# design.net
KiCad netlist of a schematic drawn in Altium Designer
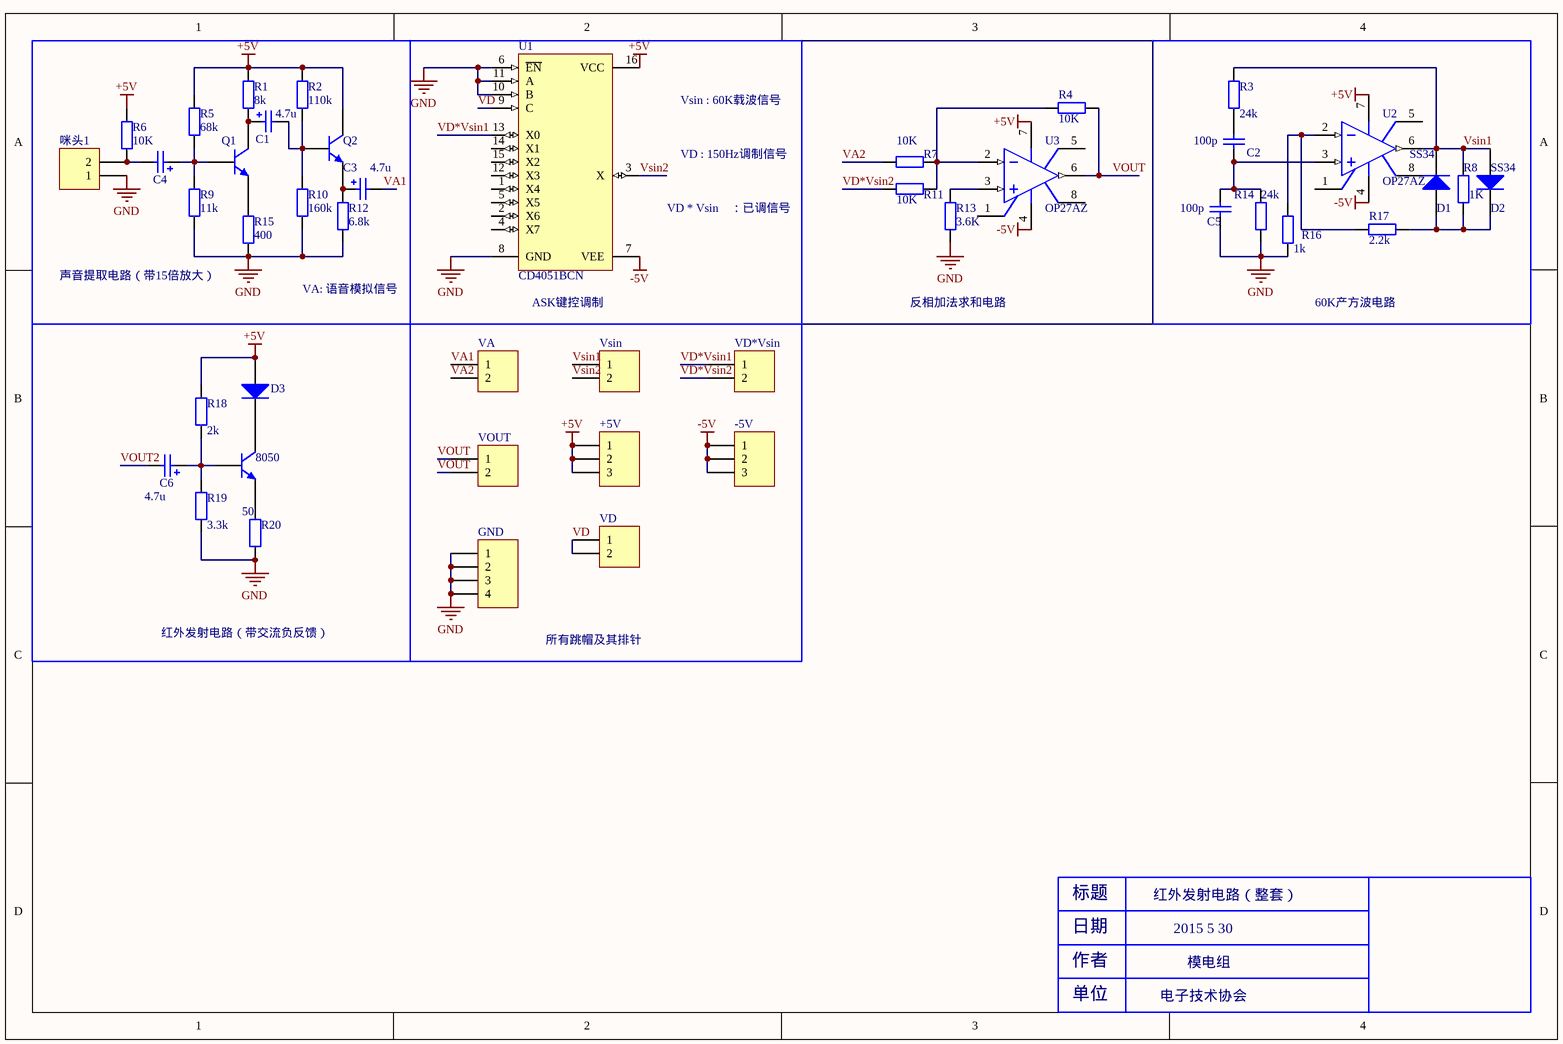
[diagram p0: 红外发射（整套）.SchDoc]

(export (version "E")
  (design (tool "Eeschema 10.0.6"))
  (components
    (comp (ref "+5V")
      (value "Header 3")
      (footprint "HDR1X3")
      (description "Header, 3-Pin")
      (fields (field (name "PUBLISHER") "Altium Limited"))
      (libsource (lib "Miscellaneous Connectors") (part "Header 3"))
    )
    (comp (ref "-5V")
      (value "Header 3")
      (footprint "HDR1X3")
      (description "Header, 3-Pin")
      (fields (field (name "PUBLISHER") "Altium Limited"))
      (libsource (lib "Miscellaneous Connectors") (part "Header 3"))
    )
    (comp (ref "8050")
      (value "NPN")
      (footprint "TO-226")
      (description "NPN Bipolar Transistor")
      (fields (field (name "PUBLISHER") "Altium Limited"))
      (libsource (lib "Miscellaneous Devices") (part "NPN"))
    )
    (comp (ref "C1")
      (value "电解电容")
      (footprint "电解电容")
      (fields (field (name "ALTIUM_UNNAMED_1") "4.7u"))
      (libsource (lib "自制库（原理图文件）") (part "电解电容"))
    )
    (comp (ref "C2")
      (value "瓷片电容")
      (footprint "瓷片电容")
      (fields (field (name "ALTIUM_UNNAMED_1") "100p"))
      (libsource (lib "自制库（原理图文件）") (part "瓷片电容"))
    )
    (comp (ref "C3")
      (value "电解电容")
      (footprint "电解电容")
      (fields (field (name "ALTIUM_UNNAMED_1") "4.7u"))
      (libsource (lib "自制库（原理图文件）") (part "电解电容"))
    )
    (comp (ref "C4") (value "电解电容") (footprint "电解电容") (libsource (lib "自制库（原理图文件）") (part "电解电容")))
    (comp (ref "C5")
      (value "瓷片电容")
      (footprint "瓷片电容")
      (fields (field (name "ALTIUM_UNNAMED_1") "100p"))
      (libsource (lib "自制库（原理图文件）") (part "瓷片电容"))
    )
    (comp (ref "C6")
      (value "电解电容")
      (footprint "电解电容")
      (fields (field (name "ALTIUM_UNNAMED_1") "4.7u"))
      (libsource (lib "自制库（原理图文件）") (part "电解电容"))
    )
    (comp (ref "D1")
      (value "SS34")
      (footprint "DO-41")
      (description "1 Amp General Purpose Rectifier")
      (fields (field (name "PUBLISHER") "Altium Limited"))
      (libsource (lib "Miscellaneous Devices") (part "Diode 1N4007"))
    )
    (comp (ref "D2")
      (value "SS34")
      (footprint "DO-41")
      (description "1 Amp General Purpose Rectifier")
      (fields (field (name "PUBLISHER") "Altium Limited"))
      (libsource (lib "Miscellaneous Devices") (part "Diode 1N4007"))
    )
    (comp (ref "D3")
      (value "Diode")
      (footprint "SMC")
      (description "Default Diode")
      (fields (field (name "PUBLISHER") "Altium Limited"))
      (libsource (lib "Miscellaneous Devices") (part "Diode"))
    )
    (comp (ref "GND")
      (value "Header 4")
      (footprint "HDR1X4")
      (description "Header, 4-Pin")
      (fields (field (name "PUBLISHER") "Altium Limited"))
      (libsource (lib "Miscellaneous Connectors") (part "Header 4"))
    )
    (comp (ref "Q1")
      (value "NPN")
      (footprint "TO-92A")
      (description "NPN Bipolar Transistor")
      (fields (field (name "PUBLISHER") "Altium Limited"))
      (libsource (lib "Miscellaneous Devices") (part "NPN"))
    )
    (comp (ref "Q2")
      (value "NPN")
      (footprint "TO-92A")
      (description "NPN Bipolar Transistor")
      (fields (field (name "PUBLISHER") "Altium Limited"))
      (libsource (lib "Miscellaneous Devices") (part "NPN"))
    )
    (comp (ref "R1")
      (value "8k")
      (footprint "AXIAL-0.4")
      (description "Resistor")
      (fields (field (name "Comment") "Res2") (field (name "PUBLISHER") "Altium Limited"))
      (libsource (lib "") (part "Res2_1"))
    )
    (comp (ref "R2")
      (value "110k")
      (footprint "AXIAL-0.4")
      (description "Resistor")
      (fields (field (name "Comment") "Res2") (field (name "PUBLISHER") "Altium Limited"))
      (libsource (lib "") (part "Res2_1"))
    )
    (comp (ref "R3")
      (value "24k")
      (footprint "AXIAL-0.4")
      (description "Resistor")
      (fields (field (name "Comment") "Res2") (field (name "PUBLISHER") "Altium Limited"))
      (libsource (lib "") (part "Res2_1"))
    )
    (comp (ref "R4")
      (value "10K")
      (footprint "AXIAL-0.4")
      (description "Resistor")
      (fields (field (name "Comment") "Res2") (field (name "PUBLISHER") "Altium Limited"))
      (libsource (lib "Miscellaneous Devices") (part "Res2"))
    )
    (comp (ref "R5")
      (value "68k")
      (footprint "AXIAL-0.4")
      (description "Resistor")
      (fields (field (name "Comment") "Res2") (field (name "PUBLISHER") "Altium Limited"))
      (libsource (lib "") (part "Res2_1"))
    )
    (comp (ref "R6")
      (value "10K")
      (footprint "AXIAL-0.4")
      (description "Resistor")
      (fields (field (name "Comment") "Res2") (field (name "PUBLISHER") "Altium Limited"))
      (libsource (lib "") (part "Res2_1"))
    )
    (comp (ref "R7")
      (value "10K")
      (footprint "AXIAL-0.4")
      (description "Resistor")
      (fields (field (name "Comment") "Res2") (field (name "PUBLISHER") "Altium Limited"))
      (libsource (lib "Miscellaneous Devices") (part "Res2"))
    )
    (comp (ref "R8")
      (value "1K")
      (footprint "AXIAL-0.4")
      (description "Resistor")
      (fields (field (name "Comment") "Res2") (field (name "PUBLISHER") "Altium Limited"))
      (libsource (lib "") (part "Res2_1"))
    )
    (comp (ref "R9")
      (value "11k")
      (footprint "AXIAL-0.4")
      (description "Resistor")
      (fields (field (name "Comment") "Res2") (field (name "PUBLISHER") "Altium Limited"))
      (libsource (lib "") (part "Res2_1"))
    )
    (comp (ref "R10")
      (value "160k")
      (footprint "AXIAL-0.4")
      (description "Resistor")
      (fields (field (name "Comment") "Res2") (field (name "PUBLISHER") "Altium Limited"))
      (libsource (lib "") (part "Res2_1"))
    )
    (comp (ref "R11")
      (value "10K")
      (footprint "AXIAL-0.4")
      (description "Resistor")
      (fields (field (name "Comment") "Res2") (field (name "PUBLISHER") "Altium Limited"))
      (libsource (lib "Miscellaneous Devices") (part "Res2"))
    )
    (comp (ref "R12")
      (value "6.8k")
      (footprint "AXIAL-0.4")
      (description "Resistor")
      (fields (field (name "Comment") "Res2") (field (name "PUBLISHER") "Altium Limited"))
      (libsource (lib "") (part "Res2_1"))
    )
    (comp (ref "R13")
      (value "3.6K")
      (footprint "AXIAL-0.4")
      (description "Resistor")
      (fields (field (name "Comment") "Res2") (field (name "PUBLISHER") "Altium Limited"))
      (libsource (lib "") (part "Res2_1"))
    )
    (comp (ref "R14")
      (value "24k")
      (footprint "AXIAL-0.4")
      (description "Resistor")
      (fields (field (name "Comment") "Res2") (field (name "PUBLISHER") "Altium Limited"))
      (libsource (lib "") (part "Res2_1"))
    )
    (comp (ref "R15")
      (value "400")
      (footprint "AXIAL-0.4")
      (description "Resistor")
      (fields (field (name "Comment") "Res2") (field (name "PUBLISHER") "Altium Limited"))
      (libsource (lib "") (part "Res2_1"))
    )
    (comp (ref "R16")
      (value "1k")
      (footprint "AXIAL-0.4")
      (description "Resistor")
      (fields (field (name "Comment") "Res2") (field (name "PUBLISHER") "Altium Limited"))
      (libsource (lib "") (part "Res2_1"))
    )
    (comp (ref "R17")
      (value "2.2k")
      (footprint "AXIAL-0.4")
      (description "Resistor")
      (fields (field (name "Comment") "Res2") (field (name "PUBLISHER") "Altium Limited"))
      (libsource (lib "Miscellaneous Devices") (part "Res2"))
    )
    (comp (ref "R18")
      (value "2k")
      (footprint "AXIAL-0.4")
      (description "Resistor")
      (fields (field (name "Comment") "Res2") (field (name "PUBLISHER") "Altium Limited"))
      (libsource (lib "") (part "Res2_1"))
    )
    (comp (ref "R19")
      (value "3.3k")
      (footprint "AXIAL-0.4")
      (description "Resistor")
      (fields (field (name "Comment") "Res2") (field (name "PUBLISHER") "Altium Limited"))
      (libsource (lib "") (part "Res2_1"))
    )
    (comp (ref "R20")
      (value "50")
      (footprint "AXIAL-0.4")
      (description "Resistor")
      (fields (field (name "Comment") "Res2") (field (name "PUBLISHER") "Altium Limited"))
      (libsource (lib "") (part "Res2_1"))
    )
    (comp (ref "U1")
      (value "CD4051BCN")
      (footprint "DIP16")
      (description "8-Channel Analog Multiplexer/Demultiplexer")
      (fields (field (name "PUBLISHER") "Altium Limited"))
      (libsource (lib "FSC Logic Multiplexer") (part "CD4051BCN"))
    )
    (comp (ref "U2")
      (value "OP27AZ")
      (footprint "DIP8")
      (description "Low-Noise, Precision Operational Amplifier")
      (fields (field (name "PUBLISHER") "Altium Limited"))
      (libsource (lib "AD Operational Amplifier") (part "OP27AZ"))
    )
    (comp (ref "U3")
      (value "OP27AZ")
      (footprint "DIP8")
      (description "Low-Noise, Precision Operational Amplifier")
      (fields (field (name "PUBLISHER") "Altium Limited"))
      (libsource (lib "AD Operational Amplifier") (part "OP27AZ"))
    )
    (comp (ref "VA")
      (value "Header 2")
      (footprint "HDR1X2")
      (description "Header, 2-Pin")
      (fields (field (name "PUBLISHER") "Altium Limited"))
      (libsource (lib "Miscellaneous Connectors") (part "Header 2"))
    )
    (comp (ref "VD")
      (value "Header 2")
      (footprint "HDR1X2")
      (description "Header, 2-Pin")
      (fields (field (name "PUBLISHER") "Altium Limited"))
      (libsource (lib "Miscellaneous Connectors") (part "Header 2"))
    )
    (comp (ref "VD*Vsin")
      (value "Header 2")
      (footprint "HDR1X2")
      (description "Header, 2-Pin")
      (fields (field (name "PUBLISHER") "Altium Limited"))
      (libsource (lib "Miscellaneous Connectors") (part "Header 2"))
    )
    (comp (ref "VOUT")
      (value "Header 2")
      (footprint "HDR1X2")
      (description "Header, 2-Pin")
      (fields (field (name "PUBLISHER") "Altium Limited"))
      (libsource (lib "Miscellaneous Connectors") (part "Header 2"))
    )
    (comp (ref "Vsin")
      (value "Header 2")
      (footprint "HDR1X2")
      (description "Header, 2-Pin")
      (fields (field (name "PUBLISHER") "Altium Limited"))
      (libsource (lib "Miscellaneous Connectors") (part "Header 2"))
    )
    (comp (ref "咪头1")
      (value "Header 2")
      (footprint "HDR1X2")
      (description "Header, 2-Pin")
      (fields (field (name "PUBLISHER") "Altium Limited"))
      (libsource (lib "") (part "Header 2_1"))
    )
  )
  (nets
    (net (code "1") (name "+5V") (class "Default")
      (node (ref "+5V") (pin "1") (pinfunction "1_1") (pintype "passive"))
      (node (ref "+5V") (pin "2") (pinfunction "2_2") (pintype "passive"))
      (node (ref "+5V") (pin "3") (pinfunction "3_3") (pintype "passive"))
      (node (ref "D3") (pin "1") (pinfunction "A_1") (pintype "passive"))
      (node (ref "Q2") (pin "1") (pinfunction "C_1") (pintype "passive"))
      (node (ref "R1") (pin "2") (pinfunction "2_2") (pintype "passive"))
      (node (ref "R18") (pin "2") (pinfunction "2_2") (pintype "passive"))
      (node (ref "R2") (pin "2") (pinfunction "2_2") (pintype "passive"))
      (node (ref "R5") (pin "2") (pinfunction "2_2") (pintype "passive"))
      (node (ref "R6") (pin "2") (pinfunction "2_2") (pintype "passive"))
      (node (ref "U1") (pin "16") (pinfunction "VCC_16") (pintype "power_in"))
      (node (ref "U2") (pin "7") (pinfunction "V+_7") (pintype "power_in"))
      (node (ref "U3") (pin "7") (pinfunction "V+_7") (pintype "power_in"))
    )
    (net (code "2") (name "-5V") (class "Default")
      (node (ref "-5V") (pin "1") (pinfunction "1_1") (pintype "passive"))
      (node (ref "-5V") (pin "2") (pinfunction "2_2") (pintype "passive"))
      (node (ref "-5V") (pin "3") (pinfunction "3_3") (pintype "passive"))
      (node (ref "U1") (pin "7") (pinfunction "VEE_7") (pintype "power_in"))
      (node (ref "U2") (pin "4") (pinfunction "V-_4") (pintype "power_in"))
      (node (ref "U3") (pin "4") (pinfunction "V-_4") (pintype "power_in"))
    )
    (net (code "3") (name "/VA1") (class "Default")
      (node (ref "C3") (pin "2") (pinfunction "2_2") (pintype "passive"))
      (node (ref "VA") (pin "1") (pinfunction "1_1") (pintype "passive"))
    )
    (net (code "4") (name "/VA2") (class "Default")
      (node (ref "R7") (pin "1") (pinfunction "1_1") (pintype "passive"))
      (node (ref "VA") (pin "2") (pinfunction "2_2") (pintype "passive"))
    )
    (net (code "5") (name "/VD") (class "Default")
      (node (ref "U1") (pin "9") (pinfunction "C_9") (pintype "input"))
      (node (ref "VD") (pin "1") (pinfunction "1_1") (pintype "passive"))
      (node (ref "VD") (pin "2") (pinfunction "2_2") (pintype "passive"))
    )
    (net (code "6") (name "/VD*Vsin1") (class "Default")
      (node (ref "U1") (pin "13") (pinfunction "X0_13") (pintype "bidirectional"))
      (node (ref "VD*Vsin") (pin "1") (pinfunction "1_1") (pintype "passive"))
    )
    (net (code "7") (name "/VD*Vsin2") (class "Default")
      (node (ref "R11") (pin "1") (pinfunction "1_1") (pintype "passive"))
      (node (ref "VD*Vsin") (pin "2") (pinfunction "2_2") (pintype "passive"))
    )
    (net (code "8") (name "/VOUT") (class "Default")
      (node (ref "R4") (pin "2") (pinfunction "2_2") (pintype "passive"))
      (node (ref "U3") (pin "6") (pinfunction "OUT_6") (pintype "output"))
      (node (ref "VOUT") (pin "1") (pinfunction "1_1") (pintype "passive"))
      (node (ref "VOUT") (pin "2") (pinfunction "2_2") (pintype "passive"))
    )
    (net (code "9") (name "/VOUT2") (class "Default")
      (node (ref "C6") (pin "2") (pinfunction "2_2") (pintype "passive"))
    )
    (net (code "10") (name "/Vsin1") (class "Default")
      (node (ref "D1") (pin "2") (pinfunction "K_2") (pintype "passive"))
      (node (ref "D2") (pin "1") (pinfunction "A_1") (pintype "passive"))
      (node (ref "R3") (pin "2") (pinfunction "2_2") (pintype "passive"))
      (node (ref "R8") (pin "2") (pinfunction "2_2") (pintype "passive"))
      (node (ref "U2") (pin "6") (pinfunction "OUT_6") (pintype "output"))
      (node (ref "Vsin") (pin "1") (pinfunction "1_1") (pintype "passive"))
    )
    (net (code "11") (name "/Vsin2") (class "Default")
      (node (ref "U1") (pin "3") (pinfunction "X_3") (pintype "bidirectional"))
      (node (ref "Vsin") (pin "2") (pinfunction "2_2") (pintype "passive"))
    )
    (net (code "12") (name "GND") (class "Default")
      (node (ref "C5") (pin "1") (pinfunction "1_1") (pintype "passive"))
      (node (ref "GND") (pin "1") (pinfunction "1_1") (pintype "passive"))
      (node (ref "GND") (pin "2") (pinfunction "2_2") (pintype "passive"))
      (node (ref "GND") (pin "3") (pinfunction "3_3") (pintype "passive"))
      (node (ref "GND") (pin "4") (pinfunction "4_4") (pintype "passive"))
      (node (ref "R10") (pin "1") (pinfunction "1_1") (pintype "passive"))
      (node (ref "R12") (pin "1") (pinfunction "1_1") (pintype "passive"))
      (node (ref "R13") (pin "1") (pinfunction "1_1") (pintype "passive"))
      (node (ref "R14") (pin "1") (pinfunction "1_1") (pintype "passive"))
      (node (ref "R15") (pin "1") (pinfunction "1_1") (pintype "passive"))
      (node (ref "R16") (pin "1") (pinfunction "1_1") (pintype "passive"))
      (node (ref "R19") (pin "1") (pinfunction "1_1") (pintype "passive"))
      (node (ref "R20") (pin "1") (pinfunction "1_1") (pintype "passive"))
      (node (ref "R9") (pin "1") (pinfunction "1_1") (pintype "passive"))
      (node (ref "U1") (pin "10") (pinfunction "B_10") (pintype "input"))
      (node (ref "U1") (pin "11") (pinfunction "A_11") (pintype "input"))
      (node (ref "U1") (pin "6") (pinfunction "~{EN}_6") (pintype "input"))
      (node (ref "U1") (pin "8") (pinfunction "GND_8") (pintype "power_in"))
      (node (ref "咪头1") (pin "1") (pinfunction "1_1") (pintype "passive"))
    )
    (net (code "13") (name "Net-(8050-B)") (class "Default")
      (node (ref "8050") (pin "2") (pinfunction "B_2") (pintype "passive"))
      (node (ref "C6") (pin "1") (pinfunction "1_1") (pintype "passive"))
      (node (ref "R18") (pin "1") (pinfunction "1_1") (pintype "passive"))
      (node (ref "R19") (pin "2") (pinfunction "2_2") (pintype "passive"))
    )
    (net (code "14") (name "Net-(8050-C)") (class "Default")
      (node (ref "8050") (pin "1") (pinfunction "C_1") (pintype "passive"))
      (node (ref "D3") (pin "2") (pinfunction "K_2") (pintype "passive"))
    )
    (net (code "15") (name "Net-(8050-E)") (class "Default")
      (node (ref "8050") (pin "3") (pinfunction "E_3") (pintype "passive"))
      (node (ref "R20") (pin "2") (pinfunction "2_2") (pintype "passive"))
    )
    (net (code "16") (name "Net-(C2-Pad2)") (class "Default")
      (node (ref "C2") (pin "2") (pinfunction "2_2") (pintype "passive"))
      (node (ref "R3") (pin "1") (pinfunction "1_1") (pintype "passive"))
    )
    (net (code "17") (name "Net-(C4-Pad2)") (class "Default")
      (node (ref "C4") (pin "2") (pinfunction "2_2") (pintype "passive"))
      (node (ref "R6") (pin "1") (pinfunction "1_1") (pintype "passive"))
      (node (ref "咪头1") (pin "2") (pinfunction "2_2") (pintype "passive"))
    )
    (net (code "18") (name "Net-(D1-A)") (class "Default")
      (node (ref "D1") (pin "1") (pinfunction "A_1") (pintype "passive"))
      (node (ref "D2") (pin "2") (pinfunction "K_2") (pintype "passive"))
      (node (ref "R17") (pin "2") (pinfunction "2_2") (pintype "passive"))
      (node (ref "R8") (pin "1") (pinfunction "1_1") (pintype "passive"))
    )
    (net (code "19") (name "Net-(Q1-B)") (class "Default")
      (node (ref "C4") (pin "1") (pinfunction "1_1") (pintype "passive"))
      (node (ref "Q1") (pin "2") (pinfunction "B_2") (pintype "passive"))
      (node (ref "R5") (pin "1") (pinfunction "1_1") (pintype "passive"))
      (node (ref "R9") (pin "2") (pinfunction "2_2") (pintype "passive"))
    )
    (net (code "20") (name "Net-(Q1-C)") (class "Default")
      (node (ref "C1") (pin "1") (pinfunction "1_1") (pintype "passive"))
      (node (ref "Q1") (pin "1") (pinfunction "C_1") (pintype "passive"))
      (node (ref "R1") (pin "1") (pinfunction "1_1") (pintype "passive"))
    )
    (net (code "21") (name "Net-(Q1-E)") (class "Default")
      (node (ref "Q1") (pin "3") (pinfunction "E_3") (pintype "passive"))
      (node (ref "R15") (pin "2") (pinfunction "2_2") (pintype "passive"))
    )
    (net (code "22") (name "Net-(Q2-B)") (class "Default")
      (node (ref "C1") (pin "2") (pinfunction "2_2") (pintype "passive"))
      (node (ref "Q2") (pin "2") (pinfunction "B_2") (pintype "passive"))
      (node (ref "R10") (pin "2") (pinfunction "2_2") (pintype "passive"))
      (node (ref "R2") (pin "1") (pinfunction "1_1") (pintype "passive"))
    )
    (net (code "23") (name "Net-(Q2-E)") (class "Default")
      (node (ref "C3") (pin "1") (pinfunction "1_1") (pintype "passive"))
      (node (ref "Q2") (pin "3") (pinfunction "E_3") (pintype "passive"))
      (node (ref "R12") (pin "2") (pinfunction "2_2") (pintype "passive"))
    )
    (net (code "24") (name "Net-(U2-IN+)") (class "Default")
      (node (ref "C2") (pin "1") (pinfunction "1_1") (pintype "passive"))
      (node (ref "C5") (pin "2") (pinfunction "2_2") (pintype "passive"))
      (node (ref "R14") (pin "2") (pinfunction "2_2") (pintype "passive"))
      (node (ref "U2") (pin "3") (pinfunction "IN+_3") (pintype "input"))
    )
    (net (code "25") (name "Net-(U2-IN-)") (class "Default")
      (node (ref "R16") (pin "2") (pinfunction "2_2") (pintype "passive"))
      (node (ref "R17") (pin "1") (pinfunction "1_1") (pintype "passive"))
      (node (ref "U2") (pin "2") (pinfunction "IN-_2") (pintype "input"))
    )
    (net (code "26") (name "Net-(U3-IN+)") (class "Default")
      (node (ref "R13") (pin "2") (pinfunction "2_2") (pintype "passive"))
      (node (ref "U3") (pin "3") (pinfunction "IN+_3") (pintype "input"))
    )
    (net (code "27") (name "Net-(U3-IN-)") (class "Default")
      (node (ref "R11") (pin "2") (pinfunction "2_2") (pintype "passive"))
      (node (ref "R4") (pin "1") (pinfunction "1_1") (pintype "passive"))
      (node (ref "R7") (pin "2") (pinfunction "2_2") (pintype "passive"))
      (node (ref "U3") (pin "2") (pinfunction "IN-_2") (pintype "input"))
    )
    (net (code "28") (name "unconnected-(U1-X1-Pad14)") (class "Default")
      (node (ref "U1") (pin "14") (pinfunction "X1_14") (pintype "bidirectional"))
    )
    (net (code "29") (name "unconnected-(U1-X2-Pad15)") (class "Default")
      (node (ref "U1") (pin "15") (pinfunction "X2_15") (pintype "bidirectional"))
    )
    (net (code "30") (name "unconnected-(U1-X3-Pad12)") (class "Default")
      (node (ref "U1") (pin "12") (pinfunction "X3_12") (pintype "bidirectional"))
    )
    (net (code "31") (name "unconnected-(U1-X4-Pad1)") (class "Default")
      (node (ref "U1") (pin "1") (pinfunction "X4_1") (pintype "bidirectional"))
    )
    (net (code "32") (name "unconnected-(U1-X5-Pad5)") (class "Default")
      (node (ref "U1") (pin "5") (pinfunction "X5_5") (pintype "bidirectional"))
    )
    (net (code "33") (name "unconnected-(U1-X6-Pad2)") (class "Default")
      (node (ref "U1") (pin "2") (pinfunction "X6_2") (pintype "bidirectional"))
    )
    (net (code "34") (name "unconnected-(U1-X7-Pad4)") (class "Default")
      (node (ref "U1") (pin "4") (pinfunction "X7_4") (pintype "bidirectional"))
    )
    (net (code "35") (name "unconnected-(U2-CMPEN-Pad1)") (class "Default")
      (node (ref "U2") (pin "1") (pinfunction "CMPEN_1") (pintype "passive"))
    )
    (net (code "36") (name "unconnected-(U2-CMPEN-Pad8)") (class "Default")
      (node (ref "U2") (pin "8") (pinfunction "CMPEN_8") (pintype "passive"))
    )
    (net (code "37") (name "unconnected-(U2-NC-Pad5)") (class "Default")
      (node (ref "U2") (pin "5") (pinfunction "NC_5") (pintype "passive"))
    )
    (net (code "38") (name "unconnected-(U3-CMPEN-Pad1)") (class "Default")
      (node (ref "U3") (pin "1") (pinfunction "CMPEN_1") (pintype "passive"))
    )
    (net (code "39") (name "unconnected-(U3-CMPEN-Pad8)") (class "Default")
      (node (ref "U3") (pin "8") (pinfunction "CMPEN_8") (pintype "passive"))
    )
    (net (code "40") (name "unconnected-(U3-NC-Pad5)") (class "Default")
      (node (ref "U3") (pin "5") (pinfunction "NC_5") (pintype "passive"))
    )
  )
)
